# -1712220203.net
KiCad netlist of a schematic drawn in Altium Designer
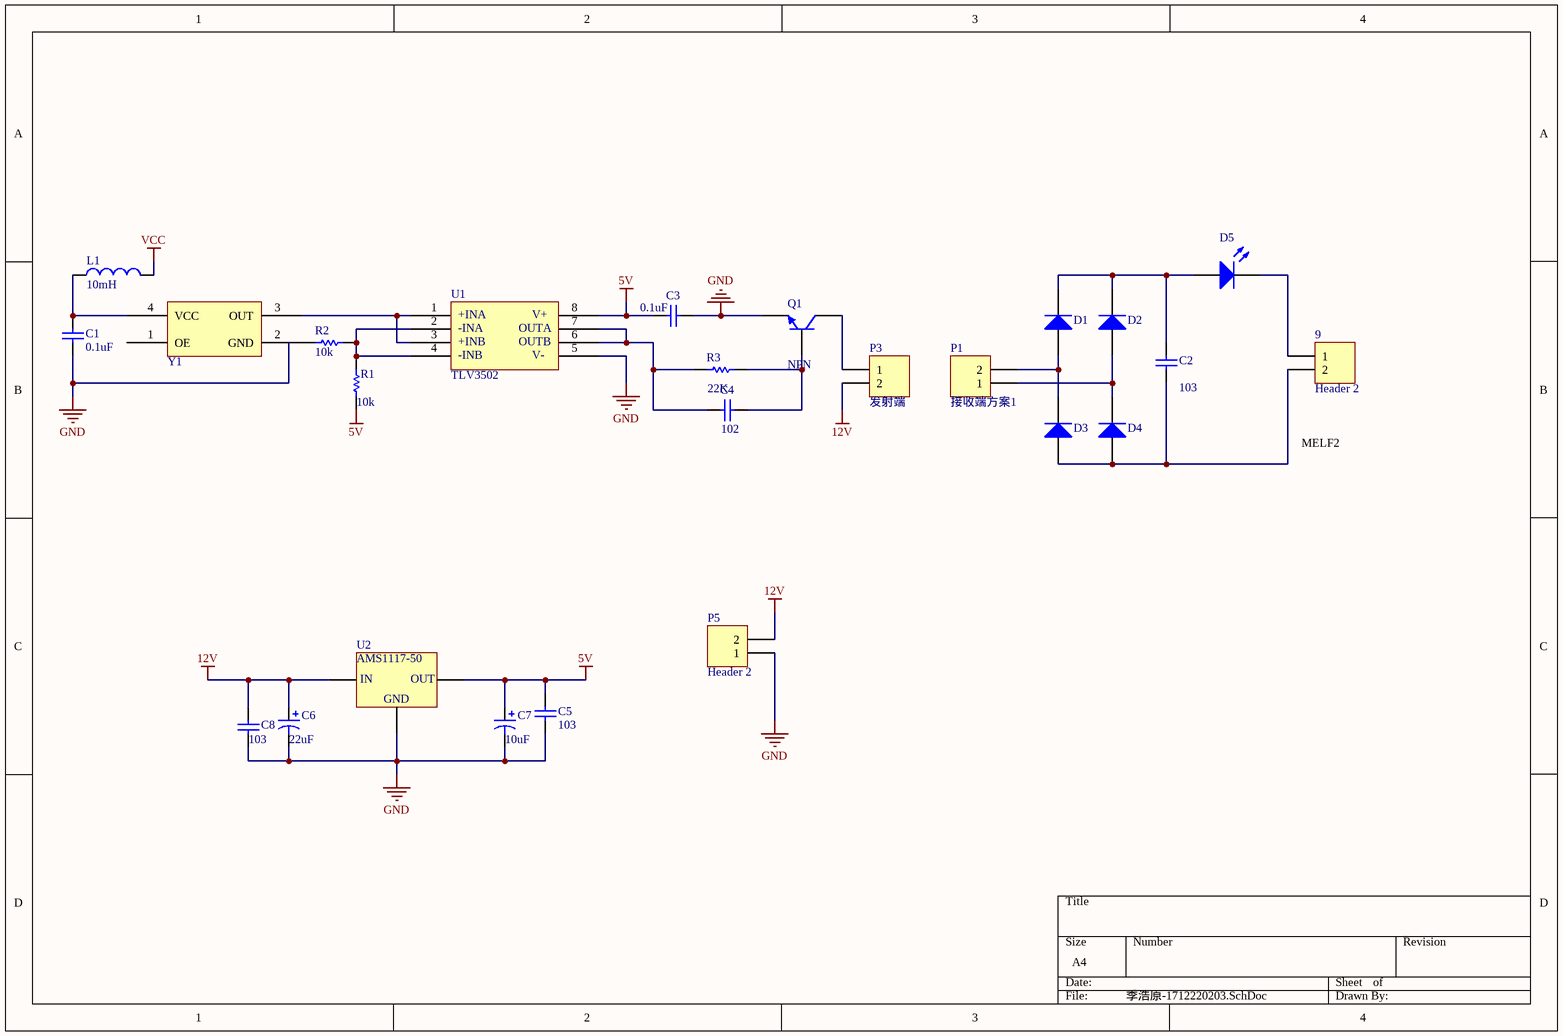
[diagram p0: 季浩原-1712220203.SchDoc]

(export (version "E")
  (design (tool "Eeschema 10.0.6"))
  (components
    (comp (ref "9")
      (value "Header 2")
      (footprint "HDR1X2")
      (description "Header, 2-Pin")
      (fields (field (name "PUBLISHER") "Altium Limited"))
      (libsource (lib "Miscellaneous Connectors") (part "Header 2"))
    )
    (comp (ref "C1")
      (value "0.1uF")
      (footprint "MELF2")
      (description "Capacitor")
      (fields (field (name "Comment") "Cap") (field (name "PUBLISHER") "Altium Limited"))
      (libsource (lib "Miscellaneous Devices") (part "Cap"))
    )
    (comp (ref "C2")
      (value "103")
      (footprint "MELF2")
      (description "Capacitor")
      (fields (field (name "Comment") "Cap") (field (name "PUBLISHER") "Altium Limited"))
      (libsource (lib "Miscellaneous Devices") (part "Cap"))
    )
    (comp (ref "C3")
      (value "0.1uF")
      (footprint "MELF2")
      (description "Capacitor")
      (fields (field (name "Comment") "Cap") (field (name "PUBLISHER") "Altium Limited"))
      (libsource (lib "Miscellaneous Devices") (part "Cap"))
    )
    (comp (ref "C4")
      (value "102")
      (footprint "MELF2")
      (description "Capacitor")
      (fields (field (name "Comment") "Cap") (field (name "PUBLISHER") "Altium Limited"))
      (libsource (lib "Miscellaneous Devices") (part "Cap"))
    )
    (comp (ref "C5")
      (value "103")
      (footprint "MELF2")
      (description "Capacitor (Semiconductor SIM Model)")
      (fields (field (name "Comment") "Cap Semi") (field (name "PUBLISHER") "Altium Limited"))
      (libsource (lib "Miscellaneous Devices") (part "Cap Semi"))
    )
    (comp (ref "C6")
      (value "22uF")
      (footprint "MELF2")
      (description "Polarized Capacitor (Radial)")
      (fields (field (name "Comment") "Cap Pol1") (field (name "PUBLISHER") "Altium Limited"))
      (libsource (lib "Miscellaneous Devices") (part "Cap Pol1"))
    )
    (comp (ref "C7")
      (value "10uF")
      (footprint "MELF2")
      (description "Polarized Capacitor (Radial)")
      (fields (field (name "Comment") "Cap Pol1") (field (name "PUBLISHER") "Altium Limited"))
      (libsource (lib "Miscellaneous Devices") (part "Cap Pol1"))
    )
    (comp (ref "C8")
      (value "103")
      (footprint "MELF2")
      (description "Capacitor")
      (fields (field (name "Comment") "Cap") (field (name "PUBLISHER") "Altium Limited"))
      (libsource (lib "Miscellaneous Devices") (part "Cap"))
    )
    (comp (ref "D1")
      (value "Diode 1N4001")
      (footprint "MELF2")
      (description "1 Amp General Purpose Rectifier")
      (fields (field (name "PUBLISHER") "Altium Limited"))
      (libsource (lib "Miscellaneous Devices") (part "Diode 1N4001"))
    )
    (comp (ref "D2")
      (value "Diode 1N4001")
      (footprint "MELF2")
      (description "1 Amp General Purpose Rectifier")
      (fields (field (name "PUBLISHER") "Altium Limited"))
      (libsource (lib "Miscellaneous Devices") (part "Diode 1N4001"))
    )
    (comp (ref "D3")
      (value "Diode 1N4001")
      (footprint "MELF2")
      (description "1 Amp General Purpose Rectifier")
      (fields (field (name "PUBLISHER") "Altium Limited"))
      (libsource (lib "Miscellaneous Devices") (part "Diode 1N4001"))
    )
    (comp (ref "D4")
      (value "Diode 1N4001")
      (footprint "MELF2")
      (description "1 Amp General Purpose Rectifier")
      (fields (field (name "PUBLISHER") "Altium Limited"))
      (libsource (lib "Miscellaneous Devices") (part "Diode 1N4001"))
    )
    (comp (ref "D5")
      (value "LED0")
      (footprint "MELF2")
      (description "Typical INFRARED GaAs LED")
      (fields (field (name "PUBLISHER") "Altium Limited"))
      (libsource (lib "Miscellaneous Devices") (part "LED0"))
    )
    (comp (ref "L1")
      (value "10mH")
      (footprint "MELF2")
      (description "Inductor")
      (fields (field (name "PUBLISHER") "Altium Limited"))
      (libsource (lib "Miscellaneous Devices") (part "Inductor"))
    )
    (comp (ref "P1")
      (value "接收端方案1")
      (footprint "SMC")
      (description "Header, 2-Pin")
      (fields (field (name "PUBLISHER") "Altium Limited"))
      (libsource (lib "") (part "Header 2_1"))
    )
    (comp (ref "P3")
      (value "发射端")
      (footprint "SMC")
      (description "Header, 2-Pin")
      (fields (field (name "PUBLISHER") "Altium Limited"))
      (libsource (lib "Miscellaneous Connectors") (part "Header 2"))
    )
    (comp (ref "P5")
      (value "Header 2")
      (footprint "HDR1X2")
      (description "Header, 2-Pin")
      (fields (field (name "PUBLISHER") "Altium Limited"))
      (libsource (lib "") (part "Header 2_1"))
    )
    (comp (ref "Q1")
      (value "NPN")
      (footprint "SOT-23")
      (description "NPN Bipolar Transistor")
      (fields (field (name "PUBLISHER") "Altium Limited"))
      (libsource (lib "Miscellaneous Devices") (part "NPN"))
    )
    (comp (ref "R1")
      (value "10k")
      (footprint "MELF2")
      (description "Semiconductor Resistor")
      (fields (field (name "Comment") "Res Semi") (field (name "PUBLISHER") "Altium Limited"))
      (libsource (lib "Miscellaneous Devices") (part "Res Semi"))
    )
    (comp (ref "R2")
      (value "10k")
      (footprint "MELF2")
      (description "Semiconductor Resistor")
      (fields (field (name "Comment") "Res Semi") (field (name "PUBLISHER") "Altium Limited"))
      (libsource (lib "Miscellaneous Devices") (part "Res Semi"))
    )
    (comp (ref "R3")
      (value "22K")
      (footprint "MELF2")
      (description "Semiconductor Resistor")
      (fields (field (name "Comment") "Res Semi") (field (name "PUBLISHER") "Altium Limited"))
      (libsource (lib "Miscellaneous Devices") (part "Res Semi"))
    )
    (comp (ref "U1") (value "TLV3502") (footprint "SO-8") (libsource (lib "Y1") (part "TLV3502")))
    (comp (ref "U2")
      (value "AMS1117-50")
      (footprint "SOT-223")
      (libsource (lib "无线充电器原理图") (part "AMS1117-50"))
    )
    (comp (ref "Y1") (value "Y?") (footprint "XTAL6") (libsource (lib "无线充电器原理图") (part "Y?")))
  )
  (nets
    (net (code "1") (name "5V") (class "Default")
      (node (ref "C3") (pin "1") (pinfunction "1_1") (pintype "passive"))
      (node (ref "C5") (pin "2") (pinfunction "2_2") (pintype "passive"))
      (node (ref "C7") (pin "1") (pinfunction "1_1") (pintype "passive"))
      (node (ref "R1") (pin "1") (pinfunction "1_1") (pintype "passive"))
      (node (ref "U1") (pin "8") (pinfunction "8_8") (pintype "passive"))
      (node (ref "U2") (pin "10") (pinfunction "10_10") (pintype "passive"))
    )
    (net (code "2") (name "12V") (class "Default")
      (node (ref "C6") (pin "1") (pinfunction "1_1") (pintype "passive"))
      (node (ref "C8") (pin "1") (pinfunction "1_1") (pintype "passive"))
      (node (ref "P3") (pin "2") (pinfunction "2_2") (pintype "passive"))
      (node (ref "P5") (pin "2") (pinfunction "2_2") (pintype "passive"))
      (node (ref "U2") (pin "11") (pinfunction "11_11") (pintype "passive"))
    )
    (net (code "3") (name "GND") (class "Default")
      (node (ref "C1") (pin "2") (pinfunction "2_2") (pintype "passive"))
      (node (ref "C3") (pin "2") (pinfunction "2_2") (pintype "passive"))
      (node (ref "C5") (pin "1") (pinfunction "1_1") (pintype "passive"))
      (node (ref "C6") (pin "2") (pinfunction "2_2") (pintype "passive"))
      (node (ref "C7") (pin "2") (pinfunction "2_2") (pintype "passive"))
      (node (ref "C8") (pin "2") (pinfunction "2_2") (pintype "passive"))
      (node (ref "P5") (pin "1") (pinfunction "1_1") (pintype "passive"))
      (node (ref "Q1") (pin "3") (pinfunction "E_3") (pintype "passive"))
      (node (ref "U1") (pin "5") (pinfunction "5_5") (pintype "passive"))
      (node (ref "U2") (pin "12") (pinfunction "12_12") (pintype "passive"))
    )
    (net (code "4") (name "Net-(C4-Pad1)") (class "Default")
      (node (ref "C4") (pin "1") (pinfunction "1_1") (pintype "passive"))
      (node (ref "R3") (pin "2") (pinfunction "2_2") (pintype "passive"))
      (node (ref "U1") (pin "6") (pinfunction "6_6") (pintype "passive"))
      (node (ref "U1") (pin "7") (pinfunction "7_7") (pintype "passive"))
    )
    (net (code "5") (name "Net-(D1-A)") (class "Default")
      (node (ref "D1") (pin "1") (pinfunction "A_1") (pintype "passive"))
      (node (ref "D3") (pin "2") (pinfunction "K_2") (pintype "passive"))
      (node (ref "P1") (pin "2") (pinfunction "2_2") (pintype "passive"))
    )
    (net (code "6") (name "Net-(D1-K)") (class "Default")
      (node (ref "C2") (pin "2") (pinfunction "2_2") (pintype "passive"))
      (node (ref "D1") (pin "2") (pinfunction "K_2") (pintype "passive"))
      (node (ref "D2") (pin "2") (pinfunction "K_2") (pintype "passive"))
      (node (ref "D5") (pin "1") (pinfunction "A_1") (pintype "passive"))
    )
    (net (code "7") (name "Net-(D2-A)") (class "Default")
      (node (ref "D2") (pin "1") (pinfunction "A_1") (pintype "passive"))
      (node (ref "D4") (pin "2") (pinfunction "K_2") (pintype "passive"))
      (node (ref "P1") (pin "1") (pinfunction "1_1") (pintype "passive"))
    )
    (net (code "8") (name "Net-(D3-A)") (class "Default")
      (node (ref "9") (pin "2") (pinfunction "2_2") (pintype "passive"))
      (node (ref "C2") (pin "1") (pinfunction "1_1") (pintype "passive"))
      (node (ref "D3") (pin "1") (pinfunction "A_1") (pintype "passive"))
      (node (ref "D4") (pin "1") (pinfunction "A_1") (pintype "passive"))
    )
    (net (code "9") (name "Net-(D5-K)") (class "Default")
      (node (ref "9") (pin "1") (pinfunction "1_1") (pintype "passive"))
      (node (ref "D5") (pin "2") (pinfunction "K_2") (pintype "passive"))
    )
    (net (code "10") (name "Net-(Q1-B)") (class "Default")
      (node (ref "C4") (pin "2") (pinfunction "2_2") (pintype "passive"))
      (node (ref "Q1") (pin "2") (pinfunction "B_2") (pintype "passive"))
      (node (ref "R3") (pin "1") (pinfunction "1_1") (pintype "passive"))
    )
    (net (code "11") (name "Net-(Q1-C)") (class "Default")
      (node (ref "P3") (pin "1") (pinfunction "1_1") (pintype "passive"))
      (node (ref "Q1") (pin "1") (pinfunction "C_1") (pintype "passive"))
    )
    (net (code "12") (name "Net-(R1-Pad2)") (class "Default")
      (node (ref "R1") (pin "2") (pinfunction "2_2") (pintype "passive"))
      (node (ref "R2") (pin "1") (pinfunction "1_1") (pintype "passive"))
      (node (ref "U1") (pin "2") (pinfunction "2_2") (pintype "passive"))
      (node (ref "U1") (pin "4") (pinfunction "4_4") (pintype "passive"))
    )
    (net (code "13") (name "Net-(Y1-GND)") (class "Default")
      (node (ref "R2") (pin "2") (pinfunction "2_2") (pintype "passive"))
      (node (ref "Y1") (pin "2") (pinfunction "GND_2") (pintype "passive"))
    )
    (net (code "14") (name "Net-(Y1-OUT)") (class "Default")
      (node (ref "U1") (pin "1") (pinfunction "1_1") (pintype "passive"))
      (node (ref "U1") (pin "3") (pinfunction "3_3") (pintype "passive"))
      (node (ref "Y1") (pin "3") (pinfunction "OUT_3") (pintype "passive"))
    )
    (net (code "15") (name "Net-(Y1-VCC)") (class "Default")
      (node (ref "C1") (pin "1") (pinfunction "1_1") (pintype "passive"))
      (node (ref "L1") (pin "1") (pinfunction "1_1") (pintype "passive"))
      (node (ref "Y1") (pin "4") (pinfunction "VCC_4") (pintype "passive"))
    )
    (net (code "16") (name "VCC") (class "Default")
      (node (ref "L1") (pin "2") (pinfunction "2_2") (pintype "passive"))
    )
    (net (code "17") (name "unconnected-(Y1-OE-Pad1)") (class "Default")
      (node (ref "Y1") (pin "1") (pinfunction "OE_1") (pintype "passive"))
    )
  )
)
